# Power_PMIC.net
KiCad netlist of a schematic drawn in Altium Designer
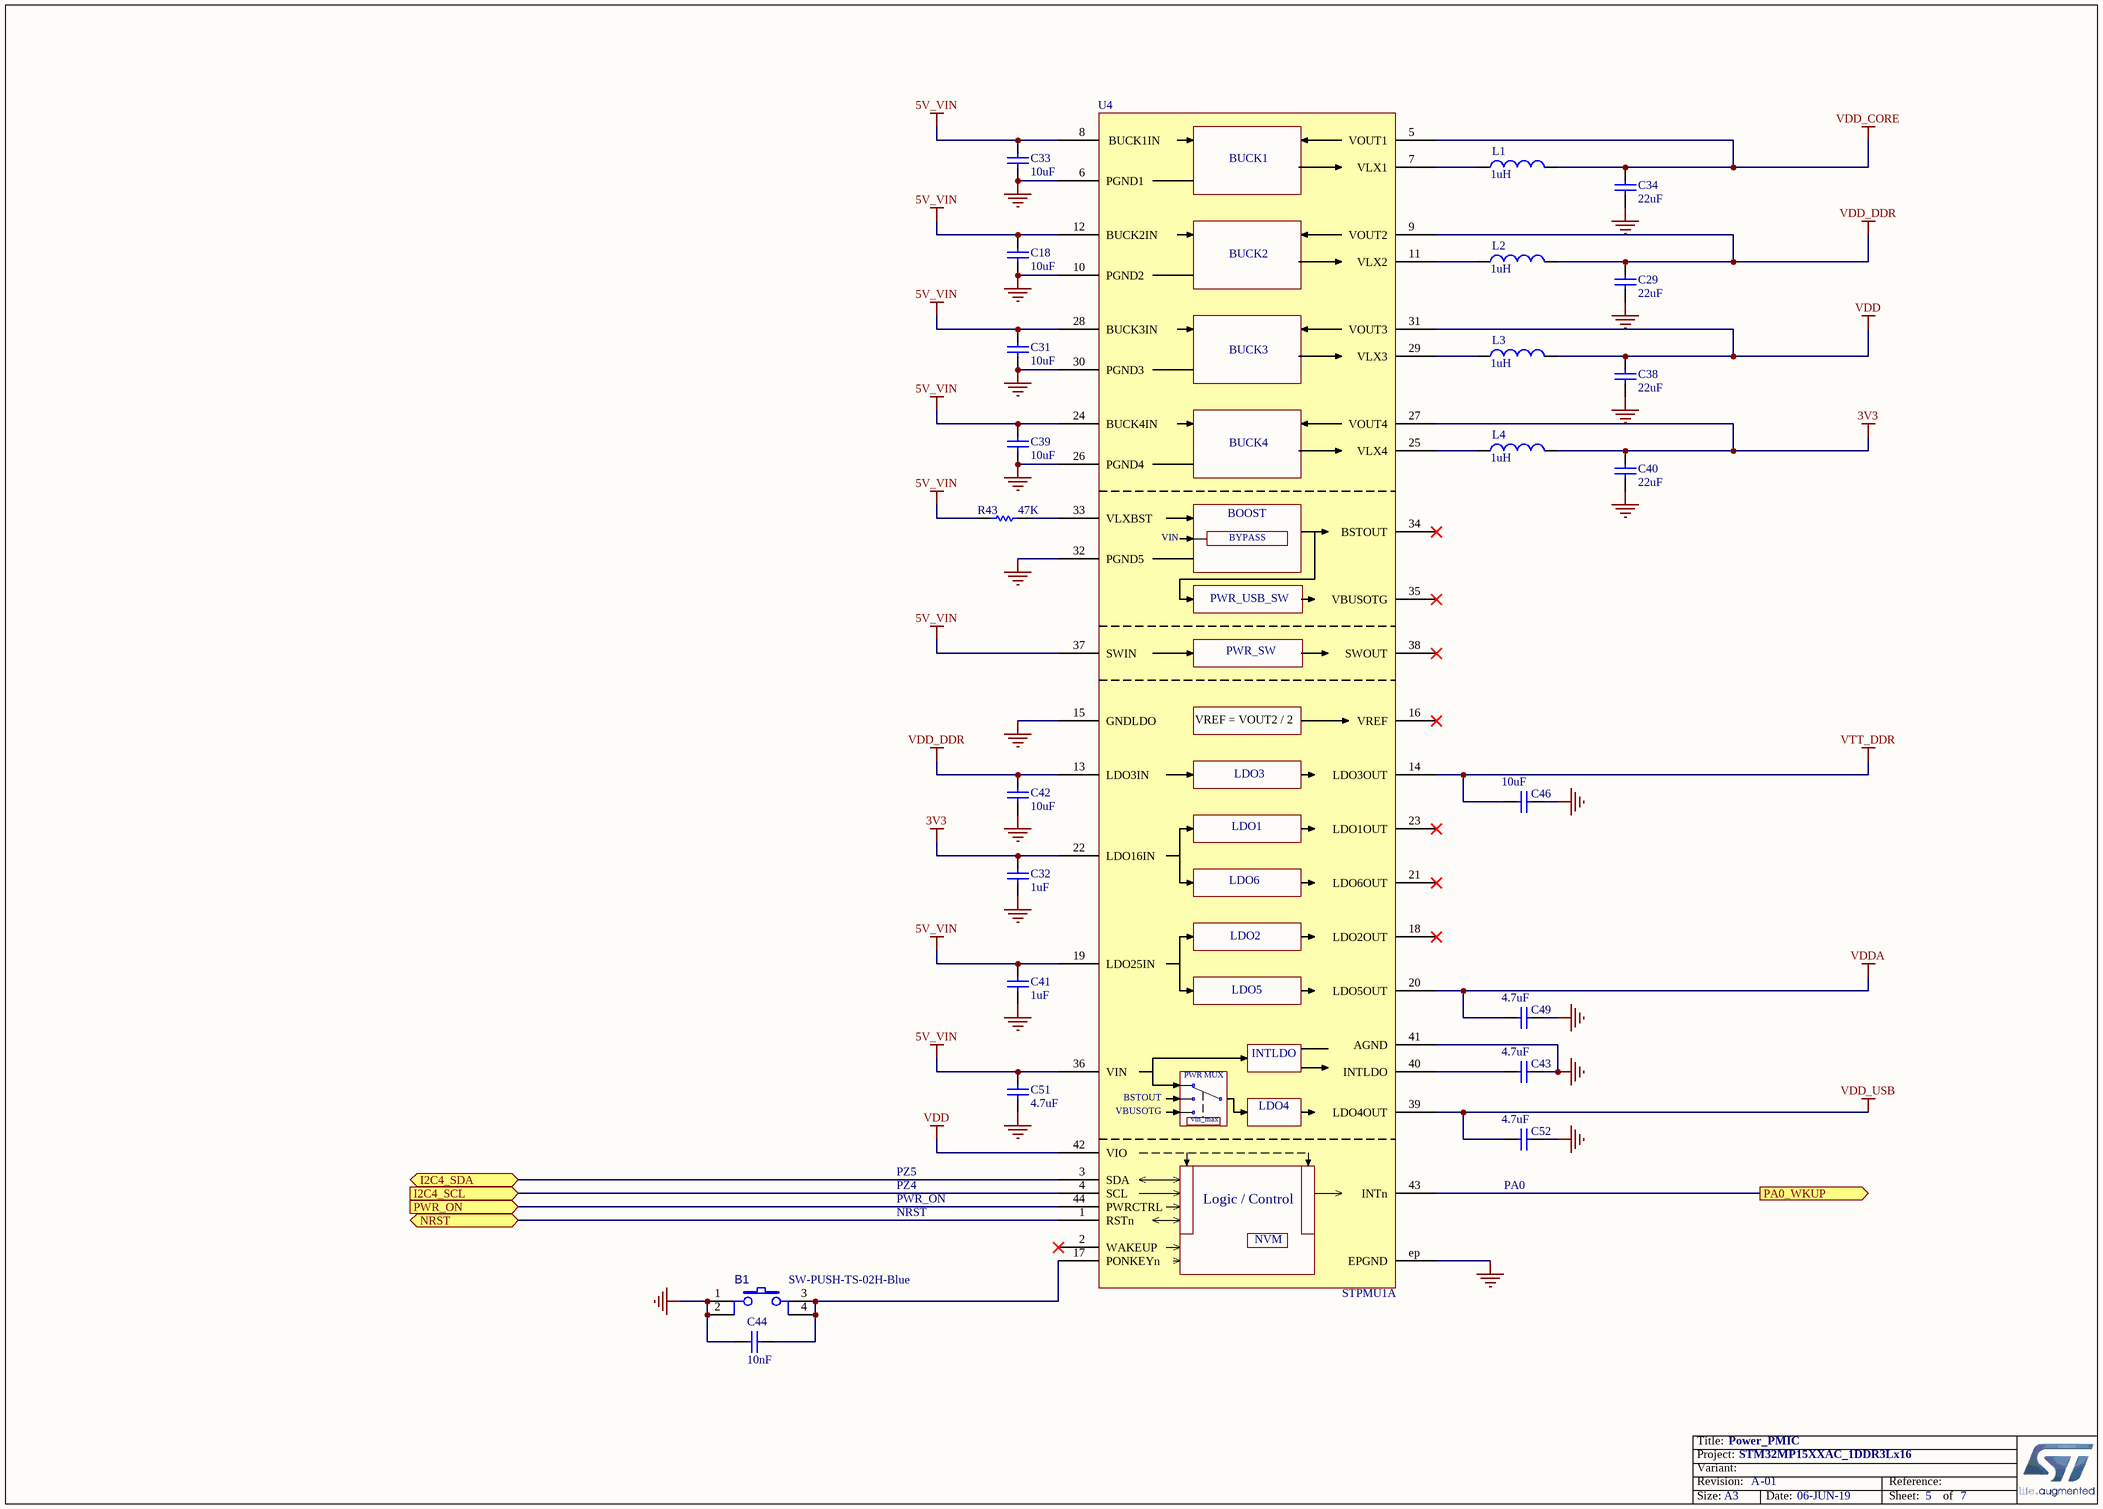
[diagram p0: Power_PMIC.SchDoc]

(export (version "E")
  (design (tool "Eeschema 10.0.6"))
  (components
    (comp (ref "B1")
      (value "SW-PUSH-TS-02H-Blue")
      (footprint "SWI_JIUBABA_C-TS-02H-2-5-B-V-T_R_BLUE")
      (description "Switch HW SMD blue")
      (fields
        (field (name "INTERNAL_PART_NUMBER") "MCD-00172")
        (field (name "MANUFACTURER_PART_NUMBER") "C-TS-02H-2.5-B-V-T/R BLUE")
        (field (name "PROVIDED_BY") "SUBCO")
      )
      (libsource (lib "MCD_PARTS_database") (part "SW-PUSH-TS-02H-Blue"))
    )
    (comp (ref "C18")
      (value "10uF")
      (footprint "C0603")
      (description "Capacitor, MLCC, 10uF, 10V, X5R, 10%, 0603, T=0,8mm")
      (fields
        (field (name "INTERNAL_PART_NUMBER") "MCD-00099")
        (field (name "MANUFACTURER_PART_NUMBER") "GRM188R61A106KE69D")
        (field (name "PROVIDED_BY") "SUBCO")
      )
      (libsource (lib "MCD_PARTS_database") (part "Capacitor"))
    )
    (comp (ref "C29")
      (value "22uF")
      (footprint "C0603")
      (description "Capacitor, MLCC, 22uF, 6V3, X5R, 20%, 0603, T=0,8mm")
      (fields
        (field (name "INTERNAL_PART_NUMBER") "MCD-00100")
        (field (name "MANUFACTURER_PART_NUMBER") "GRM188R60J226MEA0J")
        (field (name "PROVIDED_BY") "SUBCO")
      )
      (libsource (lib "MCD_PARTS_database") (part "Capacitor"))
    )
    (comp (ref "C31")
      (value "10uF")
      (footprint "C0603")
      (description "Capacitor, MLCC, 10uF, 10V, X5R, 10%, 0603, T=0,8mm")
      (fields
        (field (name "INTERNAL_PART_NUMBER") "MCD-00099")
        (field (name "MANUFACTURER_PART_NUMBER") "GRM188R61A106KE69D")
        (field (name "PROVIDED_BY") "SUBCO")
      )
      (libsource (lib "MCD_PARTS_database") (part "Capacitor"))
    )
    (comp (ref "C32")
      (value "1uF")
      (footprint "C0402")
      (description "Capacitor, MLCC, 1uF, 25V, X5R, 10%, 0402, T=0,5mm")
      (fields
        (field (name "INTERNAL_PART_NUMBER") "MCD-00095")
        (field (name "MANUFACTURER_PART_NUMBER") "GRM155R61E105KA12")
        (field (name "PROVIDED_BY") "SUBCO")
      )
      (libsource (lib "MCD_PARTS_database") (part "Capacitor"))
    )
    (comp (ref "C33")
      (value "10uF")
      (footprint "C0603")
      (description "Capacitor, MLCC, 10uF, 10V, X5R, 10%, 0603, T=0,8mm")
      (fields
        (field (name "INTERNAL_PART_NUMBER") "MCD-00099")
        (field (name "MANUFACTURER_PART_NUMBER") "GRM188R61A106KE69D")
        (field (name "PROVIDED_BY") "SUBCO")
      )
      (libsource (lib "MCD_PARTS_database") (part "Capacitor"))
    )
    (comp (ref "C34")
      (value "22uF")
      (footprint "C0603")
      (description "Capacitor, MLCC, 22uF, 6V3, X5R, 20%, 0603, T=0,8mm")
      (fields
        (field (name "INTERNAL_PART_NUMBER") "MCD-00100")
        (field (name "MANUFACTURER_PART_NUMBER") "GRM188R60J226MEA0J")
        (field (name "PROVIDED_BY") "SUBCO")
      )
      (libsource (lib "MCD_PARTS_database") (part "Capacitor"))
    )
    (comp (ref "C38")
      (value "22uF")
      (footprint "C0603")
      (description "Capacitor, MLCC, 22uF, 6V3, X5R, 20%, 0603, T=0,8mm")
      (fields
        (field (name "INTERNAL_PART_NUMBER") "MCD-00100")
        (field (name "MANUFACTURER_PART_NUMBER") "GRM188R60J226MEA0J")
        (field (name "PROVIDED_BY") "SUBCO")
      )
      (libsource (lib "MCD_PARTS_database") (part "Capacitor"))
    )
    (comp (ref "C39")
      (value "10uF")
      (footprint "C0603")
      (description "Capacitor, MLCC, 10uF, 10V, X5R, 10%, 0603, T=0,8mm")
      (fields
        (field (name "INTERNAL_PART_NUMBER") "MCD-00099")
        (field (name "MANUFACTURER_PART_NUMBER") "GRM188R61A106KE69D")
        (field (name "PROVIDED_BY") "SUBCO")
      )
      (libsource (lib "MCD_PARTS_database") (part "Capacitor"))
    )
    (comp (ref "C40")
      (value "22uF")
      (footprint "C0603")
      (description "Capacitor, MLCC, 22uF, 6V3, X5R, 20%, 0603, T=0,8mm")
      (fields
        (field (name "INTERNAL_PART_NUMBER") "MCD-00100")
        (field (name "MANUFACTURER_PART_NUMBER") "GRM188R60J226MEA0J")
        (field (name "PROVIDED_BY") "SUBCO")
      )
      (libsource (lib "MCD_PARTS_database") (part "Capacitor"))
    )
    (comp (ref "C41")
      (value "1uF")
      (footprint "C0402")
      (description "Capacitor, MLCC, 1uF, 25V, X5R, 10%, 0402, T=0,5mm")
      (fields
        (field (name "INTERNAL_PART_NUMBER") "MCD-00095")
        (field (name "MANUFACTURER_PART_NUMBER") "GRM155R61E105KA12")
        (field (name "PROVIDED_BY") "SUBCO")
      )
      (libsource (lib "MCD_PARTS_database") (part "Capacitor"))
    )
    (comp (ref "C42")
      (value "10uF")
      (footprint "C0603")
      (description "Capacitor, MLCC, 10uF, 10V, X5R, 10%, 0603, T=0,8mm")
      (fields
        (field (name "INTERNAL_PART_NUMBER") "MCD-00099")
        (field (name "MANUFACTURER_PART_NUMBER") "GRM188R61A106KE69D")
        (field (name "PROVIDED_BY") "SUBCO")
      )
      (libsource (lib "MCD_PARTS_database") (part "Capacitor"))
    )
    (comp (ref "C43")
      (value "4.7uF")
      (footprint "C0402")
      (description "Capacitor, MLCC, 4.7uF, 6V3, X5R, 20%, 0402, T=0,5mm")
      (fields
        (field (name "INTERNAL_PART_NUMBER") "MCD-00096")
        (field (name "MANUFACTURER_PART_NUMBER") "GRM155R60J475ME87")
        (field (name "PROVIDED_BY") "SUBCO")
      )
      (libsource (lib "MCD_PARTS_database") (part "Capacitor"))
    )
    (comp (ref "C44")
      (value "10nF")
      (footprint "C0402")
      (description "Capacitor, MLCC, 10nF, 16V, X7R, 10%, 0402, T=0.5mm")
      (fields
        (field (name "INTERNAL_PART_NUMBER") "MCD-00011")
        (field (name "MANUFACTURER_PART_NUMBER") "CC0402KRX7R7BB103")
        (field (name "PROVIDED_BY") "SUBCO")
      )
      (libsource (lib "MCD_PARTS_database") (part "Capacitor"))
    )
    (comp (ref "C46")
      (value "10uF")
      (footprint "C0603")
      (description "Capacitor, MLCC, 10uF, 10V, X5R, 10%, 0603, T=0,8mm")
      (fields
        (field (name "INTERNAL_PART_NUMBER") "MCD-00099")
        (field (name "MANUFACTURER_PART_NUMBER") "GRM188R61A106KE69D")
        (field (name "PROVIDED_BY") "SUBCO")
      )
      (libsource (lib "MCD_PARTS_database") (part "Capacitor"))
    )
    (comp (ref "C49")
      (value "4.7uF")
      (footprint "C0402")
      (description "Capacitor, MLCC, 4.7uF, 6V3, X5R, 20%, 0402, T=0,5mm")
      (fields
        (field (name "INTERNAL_PART_NUMBER") "MCD-00096")
        (field (name "MANUFACTURER_PART_NUMBER") "GRM155R60J475ME87")
        (field (name "PROVIDED_BY") "SUBCO")
      )
      (libsource (lib "MCD_PARTS_database") (part "Capacitor"))
    )
    (comp (ref "C51")
      (value "4.7uF")
      (footprint "C0402")
      (description "Capacitor, MLCC, 4.7uF, 6V3, X5R, 20%, 0402, T=0,5mm")
      (fields
        (field (name "INTERNAL_PART_NUMBER") "MCD-00096")
        (field (name "MANUFACTURER_PART_NUMBER") "GRM155R60J475ME87")
        (field (name "PROVIDED_BY") "SUBCO")
      )
      (libsource (lib "MCD_PARTS_database") (part "Capacitor"))
    )
    (comp (ref "C52")
      (value "4.7uF")
      (footprint "C0402")
      (description "Capacitor, MLCC, 4.7uF, 6V3, X5R, 20%, 0402, T=0,5mm")
      (fields
        (field (name "INTERNAL_PART_NUMBER") "MCD-00096")
        (field (name "MANUFACTURER_PART_NUMBER") "GRM155R60J475ME87")
        (field (name "PROVIDED_BY") "SUBCO")
      )
      (libsource (lib "MCD_PARTS_database") (part "Capacitor"))
    )
    (comp (ref "L1")
      (value "1uH")
      (footprint "IND_2520_TOKO_DFE252012P")
      (description "Power Inductor ,1uH,4.3A max,+/-20%,0.042ohm,2520")
      (fields
        (field (name "INTERNAL_PART_NUMBER") "MCD-01122")
        (field (name "MANUFACTURER_PART_NUMBER") "DFE252012P-1ROM=P2")
        (field (name "PROVIDED_BY") "SUBCO")
      )
      (libsource (lib "MCD_PARTS_database") (part "IND_1uH_42mohm_3.2A"))
    )
    (comp (ref "L2")
      (value "1uH")
      (footprint "IND_2520_TOKO_DFE252012P")
      (description "Power Inductor ,1uH,4.3A max,+/-20%,0.042ohm,2520")
      (fields
        (field (name "INTERNAL_PART_NUMBER") "MCD-01122")
        (field (name "MANUFACTURER_PART_NUMBER") "DFE252012P-1ROM=P2")
        (field (name "PROVIDED_BY") "SUBCO")
      )
      (libsource (lib "MCD_PARTS_database") (part "IND_1uH_42mohm_3.2A"))
    )
    (comp (ref "L3")
      (value "1uH")
      (footprint "IND_2520_TOKO_DFE252012P")
      (description "Power Inductor ,1uH,4.3A max,+/-20%,0.042ohm,2520")
      (fields
        (field (name "INTERNAL_PART_NUMBER") "MCD-01122")
        (field (name "MANUFACTURER_PART_NUMBER") "DFE252012P-1ROM=P2")
        (field (name "PROVIDED_BY") "SUBCO")
      )
      (libsource (lib "MCD_PARTS_database") (part "IND_1uH_42mohm_3.2A"))
    )
    (comp (ref "L4")
      (value "1uH")
      (footprint "IND_2520_TOKO_DFE252012P")
      (description "Power Inductor ,1uH,4.3A max,+/-20%,0.042ohm,2520")
      (fields
        (field (name "INTERNAL_PART_NUMBER") "MCD-01122")
        (field (name "MANUFACTURER_PART_NUMBER") "DFE252012P-1ROM=P2")
        (field (name "PROVIDED_BY") "SUBCO")
      )
      (libsource (lib "MCD_PARTS_database") (part "IND_1uH_42mohm_3.2A"))
    )
    (comp (ref "R43")
      (value "47K")
      (footprint "R0402")
      (description "Resistor,47K,0402,1%,1/16W")
      (fields
        (field (name "INTERNAL_PART_NUMBER") "MCD-00063")
        (field (name "MANUFACTURER_PART_NUMBER") "RC0402FR-0747KL")
        (field (name "PROVIDED_BY") "SUBCO")
      )
      (libsource (lib "MCD_PARTS_database") (part "Resistor"))
    )
    (comp (ref "U4")
      (value "STPMU1A")
      (footprint "ICC_WFQFN44-EPAD_5X6_P040")
      (description "STM PMIC WFQFN 5.0x6.0x0.80 44L 0.4 pitch")
      (fields
        (field (name "INTERNAL_PART_NUMBER") "MCD-00303")
        (field (name "MANUFACTURER_PART_NUMBER") "STPMU1APQR")
        (field (name "PROVIDED_BY") "SUBCO with ST control")
      )
      (libsource (lib "MCD_PARTS_database") (part "STPMU1"))
    )
  )
  (nets
    (net (code "1") (name "/I2C4_SCL") (class "Default")
      (node (ref "U4") (pin "4") (pinfunction "SCL_4") (pintype "passive"))
    )
    (net (code "2") (name "/I2C4_SDA") (class "Default")
      (node (ref "U4") (pin "3") (pinfunction "SDA_3") (pintype "passive"))
    )
    (net (code "3") (name "/NRST") (class "Default")
      (node (ref "U4") (pin "1") (pinfunction "RSTn_1") (pintype "passive"))
    )
    (net (code "4") (name "/PA0_WKUP") (class "Default")
      (node (ref "U4") (pin "43") (pinfunction "INTn_43") (pintype "passive"))
    )
    (net (code "5") (name "/PWR_ON") (class "Default")
      (node (ref "U4") (pin "44") (pinfunction "PWRCTRL_44") (pintype "passive"))
    )
    (net (code "6") (name "3V3") (class "Default")
      (node (ref "C32") (pin "2") (pinfunction "2_2") (pintype "passive"))
      (node (ref "C40") (pin "2") (pinfunction "2_2") (pintype "passive"))
      (node (ref "L4") (pin "2") (pinfunction "2_2") (pintype "passive"))
      (node (ref "U4") (pin "22") (pinfunction "LDO16IN_22") (pintype "passive"))
      (node (ref "U4") (pin "27") (pinfunction "VOUT4_27") (pintype "passive"))
    )
    (net (code "7") (name "5V_VIN") (class "Default")
      (node (ref "C18") (pin "2") (pinfunction "2_2") (pintype "passive"))
      (node (ref "C31") (pin "2") (pinfunction "2_2") (pintype "passive"))
      (node (ref "C33") (pin "2") (pinfunction "2_2") (pintype "passive"))
      (node (ref "C39") (pin "2") (pinfunction "2_2") (pintype "passive"))
      (node (ref "C41") (pin "2") (pinfunction "2_2") (pintype "passive"))
      (node (ref "C51") (pin "2") (pinfunction "2_2") (pintype "passive"))
      (node (ref "R43") (pin "2") (pinfunction "2_2") (pintype "passive"))
      (node (ref "U4") (pin "12") (pinfunction "BUCK2IN_12") (pintype "passive"))
      (node (ref "U4") (pin "19") (pinfunction "LDO25IN_19") (pintype "passive"))
      (node (ref "U4") (pin "24") (pinfunction "BUCK4IN_24") (pintype "passive"))
      (node (ref "U4") (pin "28") (pinfunction "BUCK3IN_28") (pintype "passive"))
      (node (ref "U4") (pin "36") (pinfunction "VIN_36") (pintype "passive"))
      (node (ref "U4") (pin "37") (pinfunction "SWIN_37") (pintype "passive"))
      (node (ref "U4") (pin "8") (pinfunction "BUCK1IN_8") (pintype "passive"))
    )
    (net (code "8") (name "GND") (class "Default")
      (node (ref "B1") (pin "1") (pinfunction "1_1") (pintype "passive"))
      (node (ref "B1") (pin "2") (pinfunction "2_2") (pintype "passive"))
      (node (ref "C18") (pin "1") (pinfunction "1_1") (pintype "passive"))
      (node (ref "C29") (pin "1") (pinfunction "1_1") (pintype "passive"))
      (node (ref "C31") (pin "1") (pinfunction "1_1") (pintype "passive"))
      (node (ref "C32") (pin "1") (pinfunction "1_1") (pintype "passive"))
      (node (ref "C33") (pin "1") (pinfunction "1_1") (pintype "passive"))
      (node (ref "C34") (pin "1") (pinfunction "1_1") (pintype "passive"))
      (node (ref "C38") (pin "1") (pinfunction "1_1") (pintype "passive"))
      (node (ref "C39") (pin "1") (pinfunction "1_1") (pintype "passive"))
      (node (ref "C40") (pin "1") (pinfunction "1_1") (pintype "passive"))
      (node (ref "C41") (pin "1") (pinfunction "1_1") (pintype "passive"))
      (node (ref "C42") (pin "1") (pinfunction "1_1") (pintype "passive"))
      (node (ref "C43") (pin "2") (pinfunction "2_2") (pintype "passive"))
      (node (ref "C44") (pin "1") (pinfunction "1_1") (pintype "passive"))
      (node (ref "C46") (pin "1") (pinfunction "1_1") (pintype "passive"))
      (node (ref "C49") (pin "1") (pinfunction "1_1") (pintype "passive"))
      (node (ref "C51") (pin "1") (pinfunction "1_1") (pintype "passive"))
      (node (ref "C52") (pin "1") (pinfunction "1_1") (pintype "passive"))
      (node (ref "U4") (pin "10") (pinfunction "PGND2_10") (pintype "passive"))
      (node (ref "U4") (pin "15") (pinfunction "GNDLDO_15") (pintype "passive"))
      (node (ref "U4") (pin "26") (pinfunction "PGND4_26") (pintype "passive"))
      (node (ref "U4") (pin "30") (pinfunction "PGND3_30") (pintype "passive"))
      (node (ref "U4") (pin "32") (pinfunction "PGND5_32") (pintype "passive"))
      (node (ref "U4") (pin "41") (pinfunction "AGND_41") (pintype "passive"))
      (node (ref "U4") (pin "6") (pinfunction "PGND1_6") (pintype "passive"))
      (node (ref "U4") (pin "ep") (pinfunction "EPGND_ep") (pintype "passive"))
    )
    (net (code "9") (name "Net-(U4-INTLDO)") (class "Default")
      (node (ref "C43") (pin "1") (pinfunction "1_1") (pintype "passive"))
      (node (ref "U4") (pin "40") (pinfunction "INTLDO_40") (pintype "passive"))
    )
    (net (code "10") (name "Net-(U4-PONKEYn)") (class "Default")
      (node (ref "B1") (pin "3") (pinfunction "3_3") (pintype "passive"))
      (node (ref "B1") (pin "4") (pinfunction "4_4") (pintype "passive"))
      (node (ref "C44") (pin "2") (pinfunction "2_2") (pintype "passive"))
      (node (ref "U4") (pin "17") (pinfunction "PONKEYn_17") (pintype "passive"))
    )
    (net (code "11") (name "Net-(U4-VLX1)") (class "Default")
      (node (ref "L1") (pin "1") (pinfunction "1_1") (pintype "passive"))
      (node (ref "U4") (pin "7") (pinfunction "VLX1_7") (pintype "passive"))
    )
    (net (code "12") (name "Net-(U4-VLX2)") (class "Default")
      (node (ref "L2") (pin "1") (pinfunction "1_1") (pintype "passive"))
      (node (ref "U4") (pin "11") (pinfunction "VLX2_11") (pintype "passive"))
    )
    (net (code "13") (name "Net-(U4-VLX3)") (class "Default")
      (node (ref "L3") (pin "1") (pinfunction "1_1") (pintype "passive"))
      (node (ref "U4") (pin "29") (pinfunction "VLX3_29") (pintype "passive"))
    )
    (net (code "14") (name "Net-(U4-VLX4)") (class "Default")
      (node (ref "L4") (pin "1") (pinfunction "1_1") (pintype "passive"))
      (node (ref "U4") (pin "25") (pinfunction "VLX4_25") (pintype "passive"))
    )
    (net (code "15") (name "Net-(U4-VLXBST)") (class "Default")
      (node (ref "R43") (pin "1") (pinfunction "1_1") (pintype "passive"))
      (node (ref "U4") (pin "33") (pinfunction "VLXBST_33") (pintype "passive"))
    )
    (net (code "16") (name "VDD") (class "Default")
      (node (ref "C38") (pin "2") (pinfunction "2_2") (pintype "passive"))
      (node (ref "L3") (pin "2") (pinfunction "2_2") (pintype "passive"))
      (node (ref "U4") (pin "31") (pinfunction "VOUT3_31") (pintype "passive"))
      (node (ref "U4") (pin "42") (pinfunction "VIO_42") (pintype "passive"))
    )
    (net (code "17") (name "VDDA") (class "Default")
      (node (ref "C49") (pin "2") (pinfunction "2_2") (pintype "passive"))
      (node (ref "U4") (pin "20") (pinfunction "LDO5OUT_20") (pintype "passive"))
    )
    (net (code "18") (name "VDD_CORE") (class "Default")
      (node (ref "C34") (pin "2") (pinfunction "2_2") (pintype "passive"))
      (node (ref "L1") (pin "2") (pinfunction "2_2") (pintype "passive"))
      (node (ref "U4") (pin "5") (pinfunction "VOUT1_5") (pintype "passive"))
    )
    (net (code "19") (name "VDD_DDR") (class "Default")
      (node (ref "C29") (pin "2") (pinfunction "2_2") (pintype "passive"))
      (node (ref "C42") (pin "2") (pinfunction "2_2") (pintype "passive"))
      (node (ref "L2") (pin "2") (pinfunction "2_2") (pintype "passive"))
      (node (ref "U4") (pin "13") (pinfunction "LDO3IN_13") (pintype "passive"))
      (node (ref "U4") (pin "9") (pinfunction "VOUT2_9") (pintype "passive"))
    )
    (net (code "20") (name "VDD_USB") (class "Default")
      (node (ref "C52") (pin "2") (pinfunction "2_2") (pintype "passive"))
      (node (ref "U4") (pin "39") (pinfunction "LDO4OUT_39") (pintype "passive"))
    )
    (net (code "21") (name "VTT_DDR") (class "Default")
      (node (ref "C46") (pin "2") (pinfunction "2_2") (pintype "passive"))
      (node (ref "U4") (pin "14") (pinfunction "LDO3OUT_14") (pintype "passive"))
    )
    (net (code "22") (name "unconnected-(U4-BSTOUT-Pad34)") (class "Default")
      (node (ref "U4") (pin "34") (pinfunction "BSTOUT_34") (pintype "passive+no_connect"))
    )
    (net (code "23") (name "unconnected-(U4-LDO1OUT-Pad23)") (class "Default")
      (node (ref "U4") (pin "23") (pinfunction "LDO1OUT_23") (pintype "passive+no_connect"))
    )
    (net (code "24") (name "unconnected-(U4-LDO2OUT-Pad18)") (class "Default")
      (node (ref "U4") (pin "18") (pinfunction "LDO2OUT_18") (pintype "passive+no_connect"))
    )
    (net (code "25") (name "unconnected-(U4-LDO6OUT-Pad21)") (class "Default")
      (node (ref "U4") (pin "21") (pinfunction "LDO6OUT_21") (pintype "passive+no_connect"))
    )
    (net (code "26") (name "unconnected-(U4-SWOUT-Pad38)") (class "Default")
      (node (ref "U4") (pin "38") (pinfunction "SWOUT_38") (pintype "passive+no_connect"))
    )
    (net (code "27") (name "unconnected-(U4-VBUSOTG-Pad35)") (class "Default")
      (node (ref "U4") (pin "35") (pinfunction "VBUSOTG_35") (pintype "passive+no_connect"))
    )
    (net (code "28") (name "unconnected-(U4-VREF-Pad16)") (class "Default")
      (node (ref "U4") (pin "16") (pinfunction "VREF_16") (pintype "passive+no_connect"))
    )
    (net (code "29") (name "unconnected-(U4-WAKEUP-Pad2)") (class "Default")
      (node (ref "U4") (pin "2") (pinfunction "WAKEUP_2") (pintype "passive+no_connect"))
    )
  )
)
